# tablet.net
KiCad netlist of a schematic drawn in EAGLE
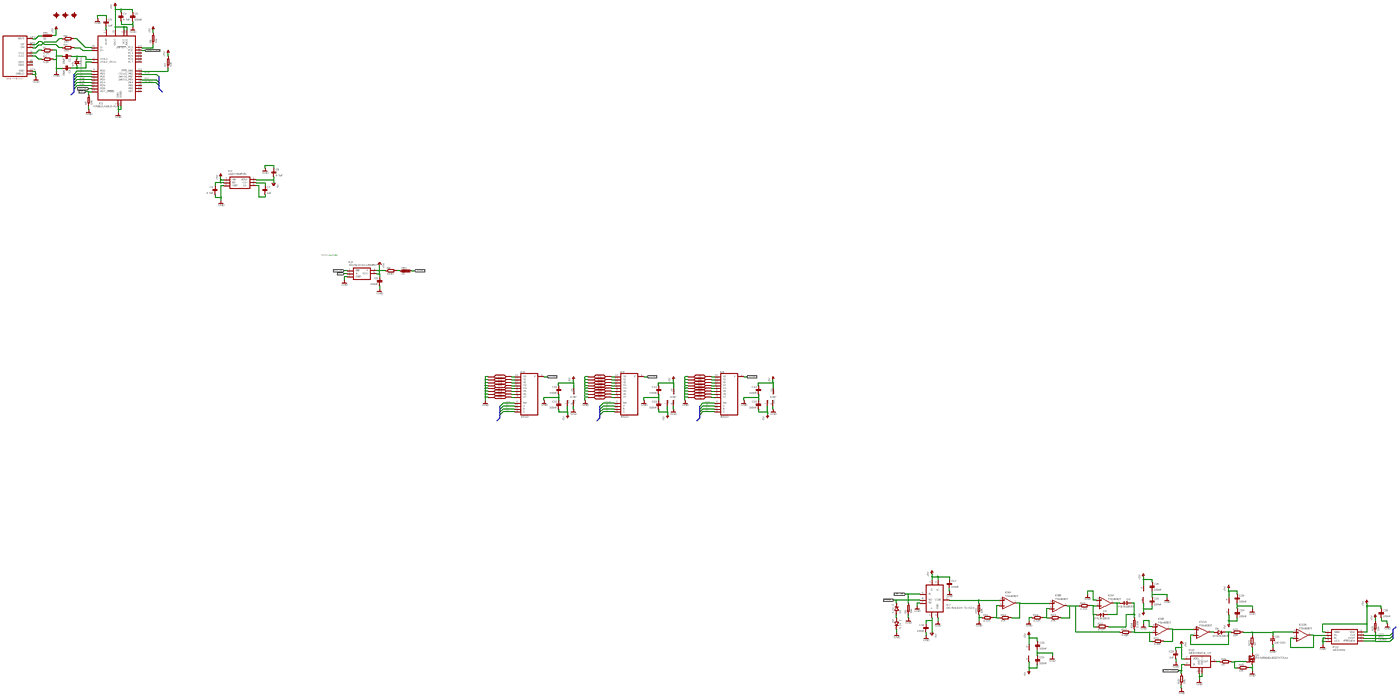
[diagram p0: schematic, sheet 1, overview]
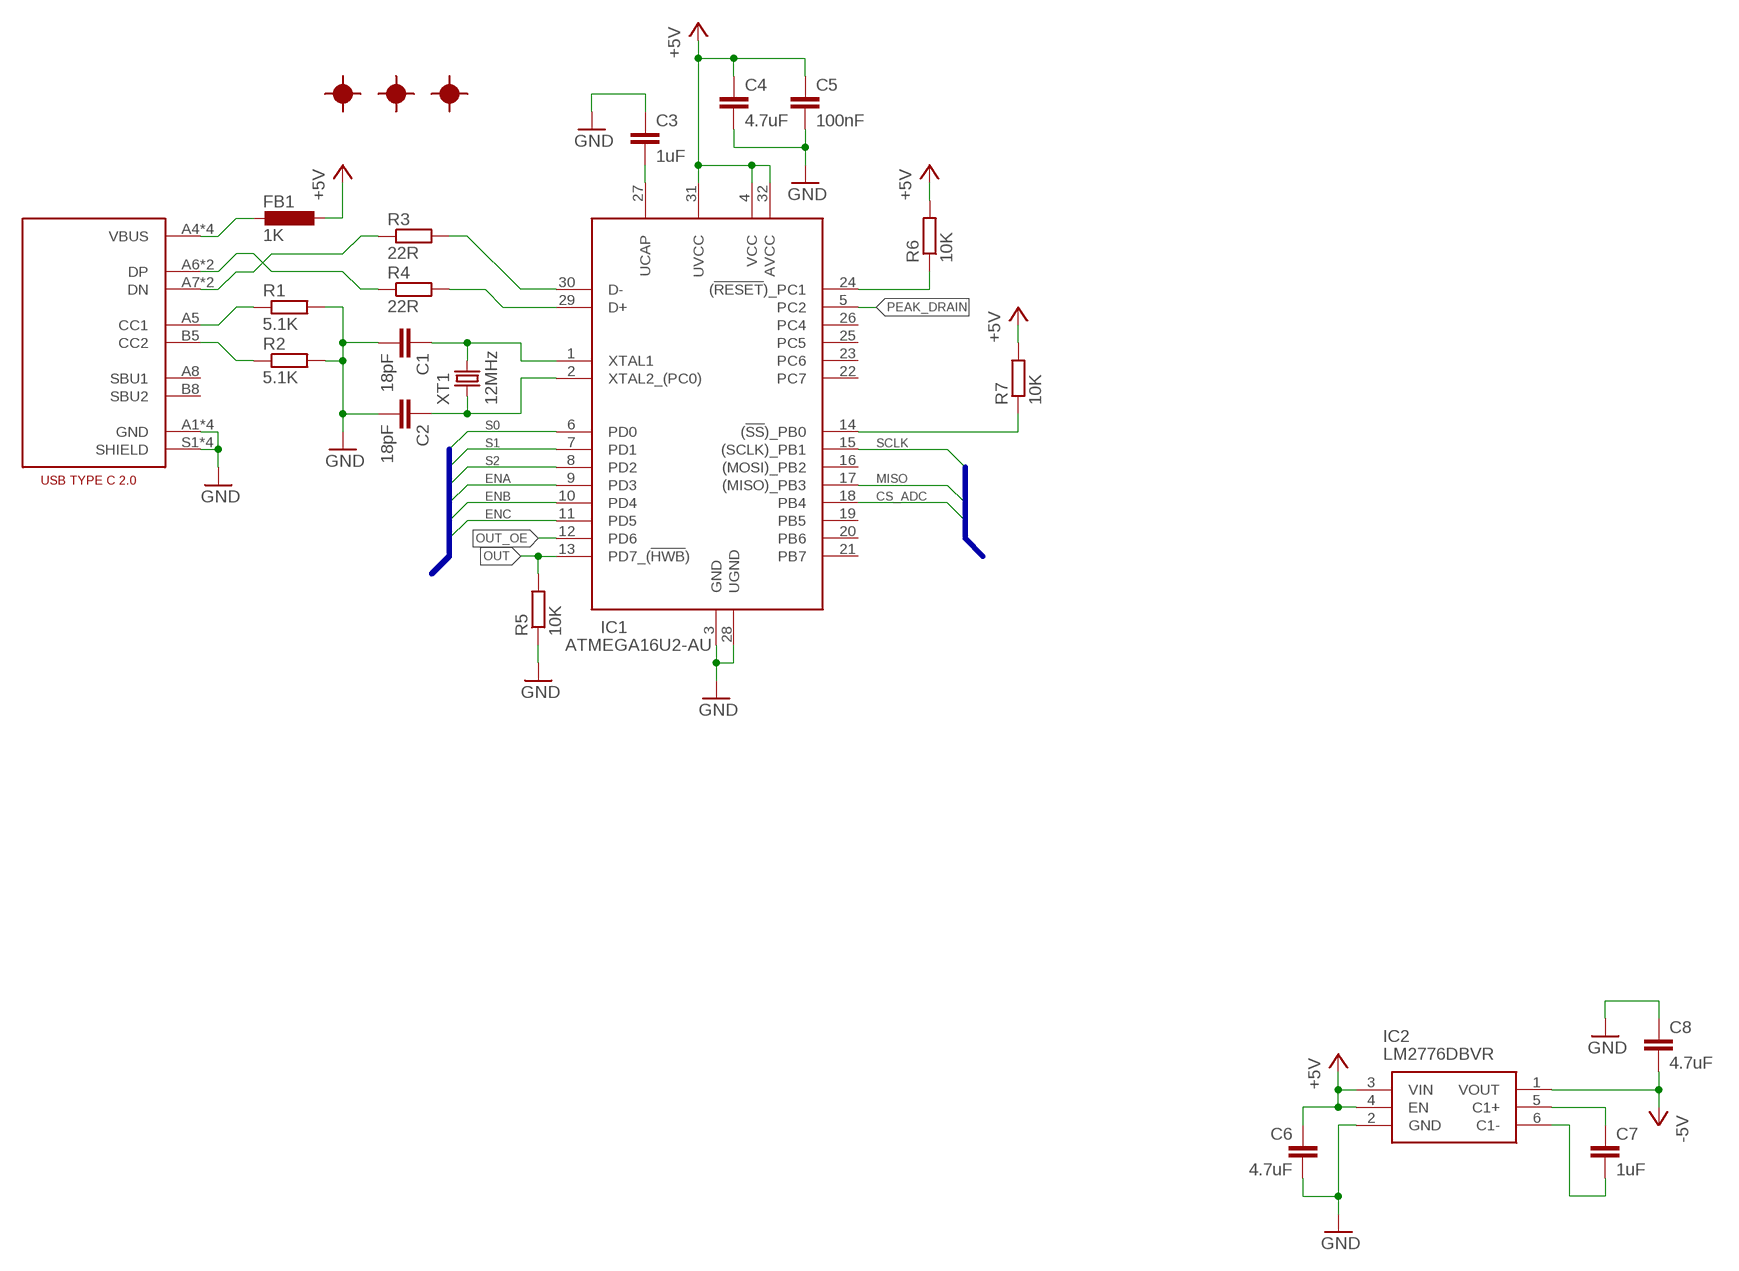
[diagram p1: schematic, sheet 1, part 1 of 4]
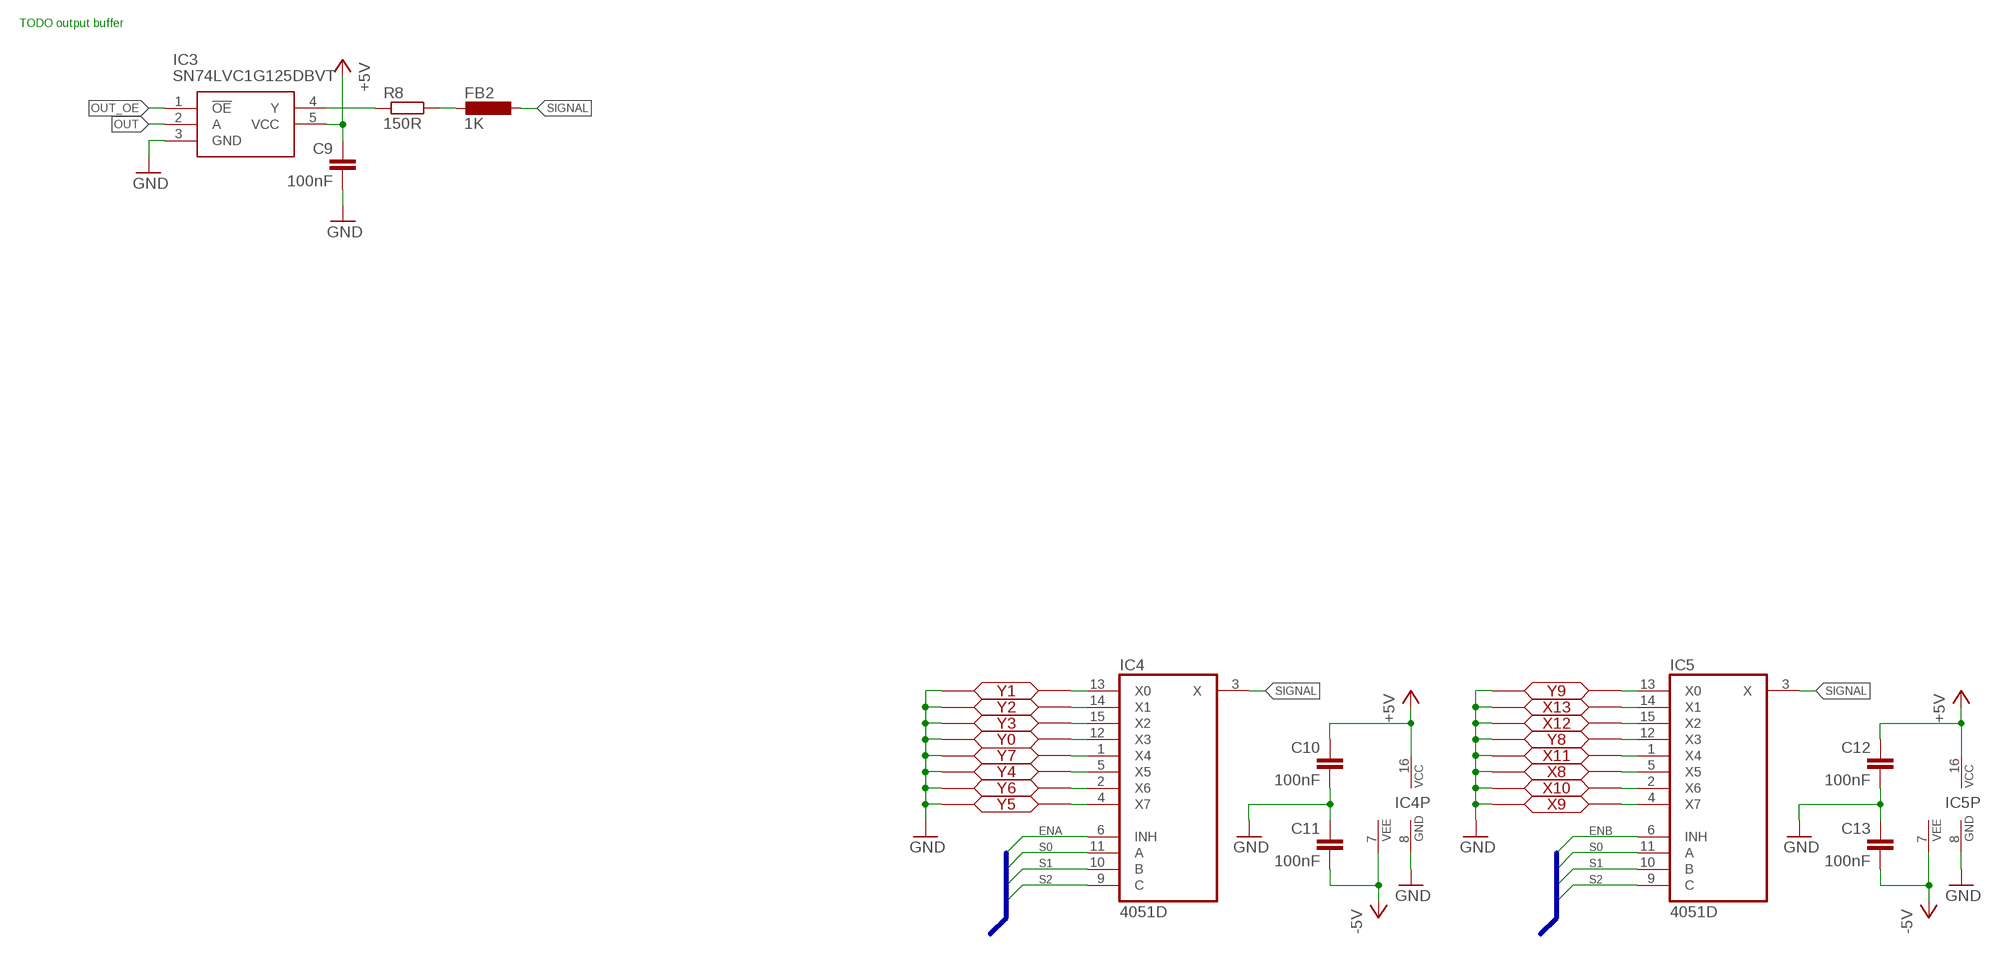
[diagram p2: schematic, sheet 1, part 2 of 4]
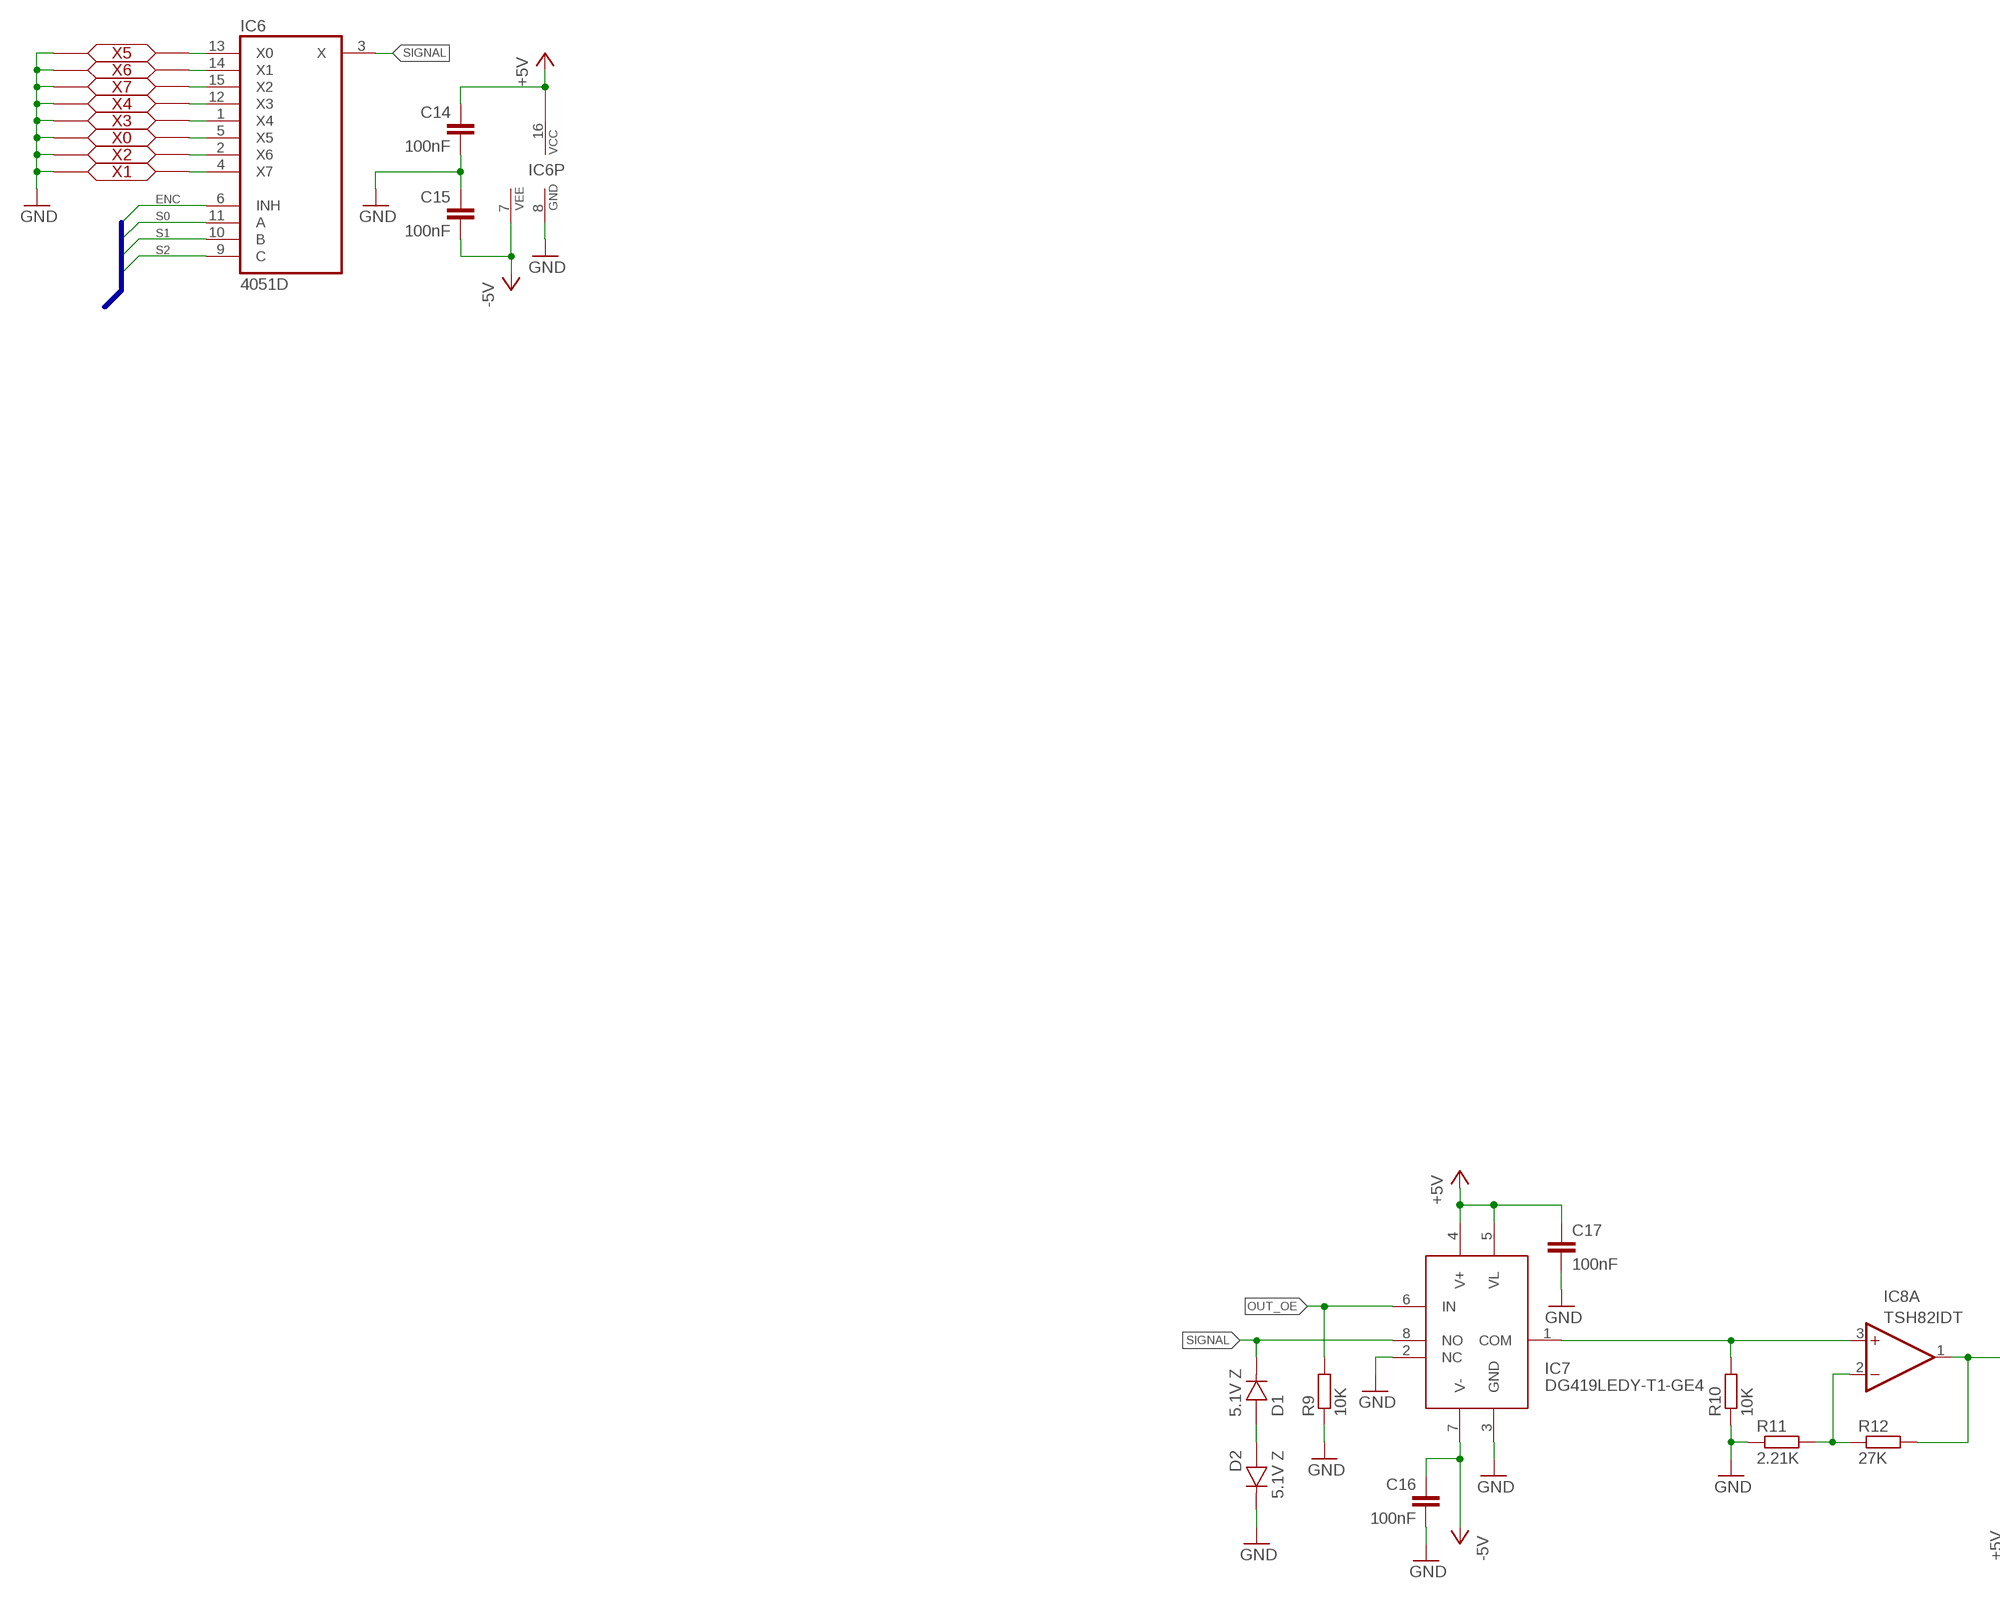
[diagram p3: schematic, sheet 1, part 3 of 4]
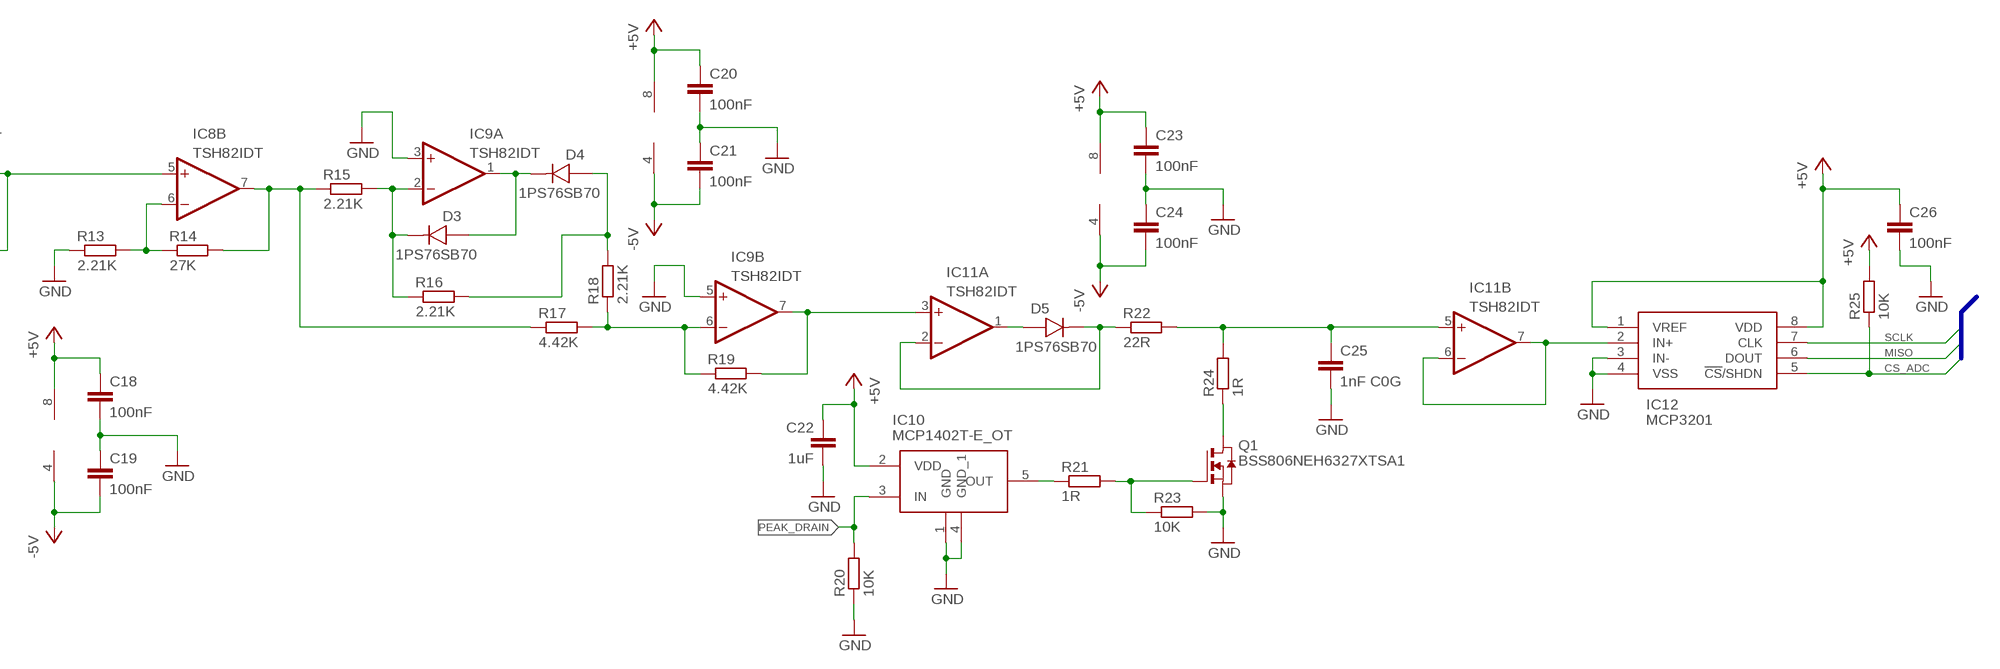
[diagram p4: schematic, sheet 1, part 4 of 4]

(export (version "E")
  (design (tool "Eeschema 10.0.6"))
  (components
    (comp (ref "C1")
      (value "18pF")
      (footprint "eagle-import:0805")
      (libsource (lib "eagle-import") (part "C0805"))
    )
    (comp (ref "C2")
      (value "18pF")
      (footprint "eagle-import:0805")
      (libsource (lib "eagle-import") (part "C0805"))
    )
    (comp (ref "C3")
      (value "1uF")
      (footprint "eagle-import:0805")
      (libsource (lib "eagle-import") (part "C0805"))
    )
    (comp (ref "C4")
      (value "4.7uF")
      (footprint "eagle-import:0805")
      (libsource (lib "eagle-import") (part "C0805"))
    )
    (comp (ref "C5")
      (value "100nF")
      (footprint "eagle-import:0805")
      (libsource (lib "eagle-import") (part "C0805"))
    )
    (comp (ref "C6")
      (value "4.7uF")
      (footprint "eagle-import:0805")
      (libsource (lib "eagle-import") (part "C0805"))
    )
    (comp (ref "C7")
      (value "1uF")
      (footprint "eagle-import:0805")
      (libsource (lib "eagle-import") (part "C0805"))
    )
    (comp (ref "C8")
      (value "4.7uF")
      (footprint "eagle-import:0805")
      (libsource (lib "eagle-import") (part "C0805"))
    )
    (comp (ref "C9")
      (value "100nF")
      (footprint "eagle-import:0805")
      (libsource (lib "eagle-import") (part "C0805"))
    )
    (comp (ref "C10")
      (value "100nF")
      (footprint "eagle-import:0805")
      (libsource (lib "eagle-import") (part "C0805"))
    )
    (comp (ref "C11")
      (value "100nF")
      (footprint "eagle-import:0805")
      (libsource (lib "eagle-import") (part "C0805"))
    )
    (comp (ref "C12")
      (value "100nF")
      (footprint "eagle-import:0805")
      (libsource (lib "eagle-import") (part "C0805"))
    )
    (comp (ref "C13")
      (value "100nF")
      (footprint "eagle-import:0805")
      (libsource (lib "eagle-import") (part "C0805"))
    )
    (comp (ref "C14")
      (value "100nF")
      (footprint "eagle-import:0805")
      (libsource (lib "eagle-import") (part "C0805"))
    )
    (comp (ref "C15")
      (value "100nF")
      (footprint "eagle-import:0805")
      (libsource (lib "eagle-import") (part "C0805"))
    )
    (comp (ref "C16")
      (value "100nF")
      (footprint "eagle-import:0805")
      (libsource (lib "eagle-import") (part "C0805"))
    )
    (comp (ref "C17")
      (value "100nF")
      (footprint "eagle-import:0805")
      (libsource (lib "eagle-import") (part "C0805"))
    )
    (comp (ref "C18")
      (value "100nF")
      (footprint "eagle-import:0805")
      (libsource (lib "eagle-import") (part "C0805"))
    )
    (comp (ref "C19")
      (value "100nF")
      (footprint "eagle-import:0805")
      (libsource (lib "eagle-import") (part "C0805"))
    )
    (comp (ref "C20")
      (value "100nF")
      (footprint "eagle-import:0805")
      (libsource (lib "eagle-import") (part "C0805"))
    )
    (comp (ref "C21")
      (value "100nF")
      (footprint "eagle-import:0805")
      (libsource (lib "eagle-import") (part "C0805"))
    )
    (comp (ref "C22")
      (value "1uF")
      (footprint "eagle-import:0805")
      (libsource (lib "eagle-import") (part "C0805"))
    )
    (comp (ref "C23")
      (value "100nF")
      (footprint "eagle-import:0805")
      (libsource (lib "eagle-import") (part "C0805"))
    )
    (comp (ref "C24")
      (value "100nF")
      (footprint "eagle-import:0805")
      (libsource (lib "eagle-import") (part "C0805"))
    )
    (comp (ref "C25")
      (value "1nF C0G")
      (footprint "eagle-import:0805")
      (libsource (lib "eagle-import") (part "C0805"))
    )
    (comp (ref "C26")
      (value "100nF")
      (footprint "eagle-import:0805")
      (libsource (lib "eagle-import") (part "C0805"))
    )
    (comp (ref "D1")
      (value "5.1V Z")
      (footprint "eagle-import:SOD323")
      (libsource (lib "eagle-import") (part "DSOD323"))
    )
    (comp (ref "D2")
      (value "5.1V Z")
      (footprint "eagle-import:SOD323")
      (libsource (lib "eagle-import") (part "DSOD323"))
    )
    (comp (ref "D3")
      (value "1PS76SB70")
      (footprint "eagle-import:SOD323")
      (libsource (lib "eagle-import") (part "DSOD323"))
    )
    (comp (ref "D4")
      (value "1PS76SB70")
      (footprint "eagle-import:SOD323")
      (libsource (lib "eagle-import") (part "DSOD323"))
    )
    (comp (ref "D5")
      (value "1PS76SB70")
      (footprint "eagle-import:SOD323")
      (libsource (lib "eagle-import") (part "DSOD323"))
    )
    (comp (ref "FB1")
      (value "1K")
      (footprint "eagle-import:0805")
      (libsource (lib "eagle-import") (part "FB0805"))
    )
    (comp (ref "FB2")
      (value "1K")
      (footprint "eagle-import:0805")
      (libsource (lib "eagle-import") (part "FB0805"))
    )
    (comp (ref "FD1")
      (value "FIDUCIAL1_2")
      (footprint "eagle-import:FIDUCIAL")
      (libsource (lib "eagle-import") (part "FIDUCIAL1_2"))
    )
    (comp (ref "FD2")
      (value "FIDUCIAL1_2")
      (footprint "eagle-import:FIDUCIAL")
      (libsource (lib "eagle-import") (part "FIDUCIAL1_2"))
    )
    (comp (ref "FD3")
      (value "FIDUCIAL1_2")
      (footprint "eagle-import:FIDUCIAL")
      (libsource (lib "eagle-import") (part "FIDUCIAL1_2"))
    )
    (comp (ref "IC1")
      (value "ATMEGA16U2-AU")
      (footprint "eagle-import:QFP80P900X900X120-32N")
      (fields
        (field (name "MOUSER_PART_NUMBER") "556-ATMEGA16U2-AU")
        (field (name "RS_PART_NUMBER") "1278282P")
      )
      (libsource (lib "eagle-import") (part "ATMEGA16U2-AU"))
    )
    (comp (ref "IC2")
      (value "LM2776DBVR")
      (footprint "eagle-import:SOT95P280X145-6N")
      (fields (field (name "MOUSER_PART_NUMBER") "595-LM2776DBVR"))
      (libsource (lib "eagle-import") (part "LM2776DBVR"))
    )
    (comp (ref "IC3")
      (value "SN74LVC1G125DBVT")
      (footprint "eagle-import:SOT95P280X145-5N")
      (fields (field (name "MOUSER_PART_NUMBER") "595-SN74LVC1G125DBVT"))
      (libsource (lib "eagle-import") (part "SN74LVC1G125DBVT"))
    )
    (comp (ref "IC4")
      (value "4051D")
      (footprint "eagle-import:SO16")
      (libsource (lib "eagle-import") (part "4051D"))
    )
    (comp (ref "IC5")
      (value "4051D")
      (footprint "eagle-import:SO16")
      (libsource (lib "eagle-import") (part "4051D"))
    )
    (comp (ref "IC6")
      (value "4051D")
      (footprint "eagle-import:SO16")
      (libsource (lib "eagle-import") (part "4051D"))
    )
    (comp (ref "IC7")
      (value "DG419LEDY-T1-GE4")
      (footprint "eagle-import:SOIC8")
      (libsource (lib "eagle-import") (part "DG419LEDY-T1-GE4"))
    )
    (comp (ref "IC8")
      (value "TSH82IDT")
      (footprint "eagle-import:SOIC8")
      (libsource (lib "eagle-import") (part "OPAMPSOIC8"))
    )
    (comp (ref "IC9")
      (value "TSH82IDT")
      (footprint "eagle-import:SOIC8")
      (libsource (lib "eagle-import") (part "OPAMPSOIC8"))
    )
    (comp (ref "IC10")
      (value "MCP1402T-E_OT")
      (footprint "eagle-import:SOT95P270X145-5N")
      (fields
        (field (name "ARROW_PART_NUMBER") "MCP1402T-E/OT")
        (field (name "MOUSER_PART_NUMBER") "579-MCP1402T-E/OT")
      )
      (libsource (lib "eagle-import") (part "MCP1402T-E_OT"))
    )
    (comp (ref "IC11")
      (value "TSH82IDT")
      (footprint "eagle-import:SOIC8")
      (libsource (lib "eagle-import") (part "OPAMPSOIC8"))
    )
    (comp (ref "IC12")
      (value "MCP3201")
      (footprint "eagle-import:SOIC8")
      (libsource (lib "eagle-import") (part "MCP3201"))
    )
    (comp (ref "J1")
      (value "USB4085-GF-A")
      (footprint "eagle-import:USB4085-GF-A")
      (libsource (lib "eagle-import") (part "USB4085-GF-A"))
    )
    (comp (ref "Q1")
      (value "BSS806NEH6327XTSA1")
      (footprint "eagle-import:SOT23_3")
      (libsource (lib "eagle-import") (part "MOSFET_NSOT23_3_GSD"))
    )
    (comp (ref "R1")
      (value "5.1K")
      (footprint "eagle-import:0805")
      (libsource (lib "eagle-import") (part "R0805"))
    )
    (comp (ref "R2")
      (value "5.1K")
      (footprint "eagle-import:0805")
      (libsource (lib "eagle-import") (part "R0805"))
    )
    (comp (ref "R3")
      (value "22R")
      (footprint "eagle-import:0805")
      (libsource (lib "eagle-import") (part "R0805"))
    )
    (comp (ref "R4")
      (value "22R")
      (footprint "eagle-import:0805")
      (libsource (lib "eagle-import") (part "R0805"))
    )
    (comp (ref "R5")
      (value "10K")
      (footprint "eagle-import:0805")
      (libsource (lib "eagle-import") (part "R0805"))
    )
    (comp (ref "R6")
      (value "10K")
      (footprint "eagle-import:0805")
      (libsource (lib "eagle-import") (part "R0805"))
    )
    (comp (ref "R7")
      (value "10K")
      (footprint "eagle-import:0805")
      (libsource (lib "eagle-import") (part "R0805"))
    )
    (comp (ref "R8")
      (value "150R")
      (footprint "eagle-import:0805")
      (libsource (lib "eagle-import") (part "R0805"))
    )
    (comp (ref "R9")
      (value "10K")
      (footprint "eagle-import:0805")
      (libsource (lib "eagle-import") (part "R0805"))
    )
    (comp (ref "R10")
      (value "10K")
      (footprint "eagle-import:0805")
      (libsource (lib "eagle-import") (part "R0805"))
    )
    (comp (ref "R11")
      (value "2.21K")
      (footprint "eagle-import:0805")
      (libsource (lib "eagle-import") (part "R0805"))
    )
    (comp (ref "R12")
      (value "27K")
      (footprint "eagle-import:0805")
      (libsource (lib "eagle-import") (part "R0805"))
    )
    (comp (ref "R13")
      (value "2.21K")
      (footprint "eagle-import:0805")
      (libsource (lib "eagle-import") (part "R0805"))
    )
    (comp (ref "R14")
      (value "27K")
      (footprint "eagle-import:0805")
      (libsource (lib "eagle-import") (part "R0805"))
    )
    (comp (ref "R15")
      (value "2.21K")
      (footprint "eagle-import:0805")
      (libsource (lib "eagle-import") (part "R0805"))
    )
    (comp (ref "R16")
      (value "2.21K")
      (footprint "eagle-import:0805")
      (libsource (lib "eagle-import") (part "R0805"))
    )
    (comp (ref "R17")
      (value "4.42K")
      (footprint "eagle-import:0805")
      (libsource (lib "eagle-import") (part "R0805"))
    )
    (comp (ref "R18")
      (value "2.21K")
      (footprint "eagle-import:0805")
      (libsource (lib "eagle-import") (part "R0805"))
    )
    (comp (ref "R19")
      (value "4.42K")
      (footprint "eagle-import:0805")
      (libsource (lib "eagle-import") (part "R0805"))
    )
    (comp (ref "R20")
      (value "10K")
      (footprint "eagle-import:0805")
      (libsource (lib "eagle-import") (part "R0805"))
    )
    (comp (ref "R21")
      (value "1R")
      (footprint "eagle-import:0805")
      (libsource (lib "eagle-import") (part "R0805"))
    )
    (comp (ref "R22")
      (value "22R")
      (footprint "eagle-import:0805")
      (libsource (lib "eagle-import") (part "R0805"))
    )
    (comp (ref "R23")
      (value "10K")
      (footprint "eagle-import:0805")
      (libsource (lib "eagle-import") (part "R0805"))
    )
    (comp (ref "R24")
      (value "1R")
      (footprint "eagle-import:0805")
      (libsource (lib "eagle-import") (part "R0805"))
    )
    (comp (ref "R25")
      (value "10K")
      (footprint "eagle-import:0805")
      (libsource (lib "eagle-import") (part "R0805"))
    )
    (comp (ref "X0") (value "2P") (footprint "eagle-import:2P") (libsource (lib "eagle-import") (part "2P")))
    (comp (ref "X1") (value "2P") (footprint "eagle-import:2P") (libsource (lib "eagle-import") (part "2P")))
    (comp (ref "X2") (value "2P") (footprint "eagle-import:2P") (libsource (lib "eagle-import") (part "2P")))
    (comp (ref "X3") (value "2P") (footprint "eagle-import:2P") (libsource (lib "eagle-import") (part "2P")))
    (comp (ref "X4") (value "2P") (footprint "eagle-import:2P") (libsource (lib "eagle-import") (part "2P")))
    (comp (ref "X5") (value "2P") (footprint "eagle-import:2P") (libsource (lib "eagle-import") (part "2P")))
    (comp (ref "X6") (value "2P") (footprint "eagle-import:2P") (libsource (lib "eagle-import") (part "2P")))
    (comp (ref "X7") (value "2P") (footprint "eagle-import:2P") (libsource (lib "eagle-import") (part "2P")))
    (comp (ref "X8") (value "2P") (footprint "eagle-import:2P") (libsource (lib "eagle-import") (part "2P")))
    (comp (ref "X9") (value "2P") (footprint "eagle-import:2P") (libsource (lib "eagle-import") (part "2P")))
    (comp (ref "X10") (value "2P") (footprint "eagle-import:2P") (libsource (lib "eagle-import") (part "2P")))
    (comp (ref "X11") (value "2P") (footprint "eagle-import:2P") (libsource (lib "eagle-import") (part "2P")))
    (comp (ref "X12") (value "2P") (footprint "eagle-import:2P") (libsource (lib "eagle-import") (part "2P")))
    (comp (ref "X13") (value "2P") (footprint "eagle-import:2P") (libsource (lib "eagle-import") (part "2P")))
    (comp (ref "XT1")
      (value "12MHz")
      (footprint "eagle-import:HC49UP")
      (libsource (lib "eagle-import") (part "CRYSTALHC49UP"))
    )
    (comp (ref "Y0") (value "2P") (footprint "eagle-import:2P") (libsource (lib "eagle-import") (part "2P")))
    (comp (ref "Y1") (value "2P") (footprint "eagle-import:2P") (libsource (lib "eagle-import") (part "2P")))
    (comp (ref "Y2") (value "2P") (footprint "eagle-import:2P") (libsource (lib "eagle-import") (part "2P")))
    (comp (ref "Y3") (value "2P") (footprint "eagle-import:2P") (libsource (lib "eagle-import") (part "2P")))
    (comp (ref "Y4") (value "2P") (footprint "eagle-import:2P") (libsource (lib "eagle-import") (part "2P")))
    (comp (ref "Y5") (value "2P") (footprint "eagle-import:2P") (libsource (lib "eagle-import") (part "2P")))
    (comp (ref "Y6") (value "2P") (footprint "eagle-import:2P") (libsource (lib "eagle-import") (part "2P")))
    (comp (ref "Y7") (value "2P") (footprint "eagle-import:2P") (libsource (lib "eagle-import") (part "2P")))
    (comp (ref "Y8") (value "2P") (footprint "eagle-import:2P") (libsource (lib "eagle-import") (part "2P")))
    (comp (ref "Y9") (value "2P") (footprint "eagle-import:2P") (libsource (lib "eagle-import") (part "2P")))
  )
  (nets
    (net (code "1") (name "+5V") (class "Default")
      (node (ref "C10") (pin "1") (pinfunction "1_1") (pintype "passive"))
      (node (ref "C12") (pin "1") (pinfunction "1_1") (pintype "passive"))
      (node (ref "C14") (pin "1") (pinfunction "1_1") (pintype "passive"))
      (node (ref "C17") (pin "1") (pinfunction "1_1") (pintype "passive"))
      (node (ref "C18") (pin "1") (pinfunction "1_1") (pintype "passive"))
      (node (ref "C20") (pin "1") (pinfunction "1_1") (pintype "passive"))
      (node (ref "C22") (pin "1") (pinfunction "1_1") (pintype "passive"))
      (node (ref "C23") (pin "1") (pinfunction "1_1") (pintype "passive"))
      (node (ref "C26") (pin "1") (pinfunction "1_1") (pintype "passive"))
      (node (ref "C4") (pin "1") (pinfunction "1_1") (pintype "passive"))
      (node (ref "C5") (pin "1") (pinfunction "1_1") (pintype "passive"))
      (node (ref "C6") (pin "1") (pinfunction "1_1") (pintype "passive"))
      (node (ref "C9") (pin "1") (pinfunction "1_1") (pintype "passive"))
      (node (ref "FB1") (pin "1") (pinfunction "1_1") (pintype "passive"))
      (node (ref "IC1") (pin "31") (pinfunction "UVCC_31") (pintype "bidirectional"))
      (node (ref "IC1") (pin "32") (pinfunction "AVCC_32") (pintype "bidirectional"))
      (node (ref "IC1") (pin "4") (pinfunction "VCC_4") (pintype "bidirectional"))
      (node (ref "IC10") (pin "2") (pinfunction "VDD_2") (pintype "power_in"))
      (node (ref "IC11") (pin "8") (pinfunction "V+_8") (pintype "power_in"))
      (node (ref "IC12") (pin "1") (pinfunction "VREF_1") (pintype "input"))
      (node (ref "IC12") (pin "8") (pinfunction "VDD_8") (pintype "power_in"))
      (node (ref "IC2") (pin "3") (pinfunction "VIN_3") (pintype "bidirectional"))
      (node (ref "IC2") (pin "4") (pinfunction "EN_4") (pintype "bidirectional"))
      (node (ref "IC3") (pin "5") (pinfunction "VCC_5") (pintype "bidirectional"))
      (node (ref "IC4") (pin "16") (pinfunction "VCC_16") (pintype "power_in"))
      (node (ref "IC5") (pin "16") (pinfunction "VCC_16") (pintype "power_in"))
      (node (ref "IC6") (pin "16") (pinfunction "VCC_16") (pintype "power_in"))
      (node (ref "IC7") (pin "4") (pinfunction "V+_4") (pintype "bidirectional"))
      (node (ref "IC7") (pin "5") (pinfunction "VL_5") (pintype "bidirectional"))
      (node (ref "IC8") (pin "8") (pinfunction "V+_8") (pintype "power_in"))
      (node (ref "IC9") (pin "8") (pinfunction "V+_8") (pintype "power_in"))
      (node (ref "R25") (pin "2") (pinfunction "2_2") (pintype "passive"))
      (node (ref "R6") (pin "2") (pinfunction "2_2") (pintype "passive"))
      (node (ref "R7") (pin "2") (pinfunction "2_2") (pintype "passive"))
    )
    (net (code "2") (name "-5V") (class "Default")
      (node (ref "C11") (pin "2") (pinfunction "2_2") (pintype "passive"))
      (node (ref "C13") (pin "2") (pinfunction "2_2") (pintype "passive"))
      (node (ref "C15") (pin "2") (pinfunction "2_2") (pintype "passive"))
      (node (ref "C16") (pin "1") (pinfunction "1_1") (pintype "passive"))
      (node (ref "C19") (pin "2") (pinfunction "2_2") (pintype "passive"))
      (node (ref "C21") (pin "2") (pinfunction "2_2") (pintype "passive"))
      (node (ref "C24") (pin "2") (pinfunction "2_2") (pintype "passive"))
      (node (ref "C8") (pin "2") (pinfunction "2_2") (pintype "passive"))
      (node (ref "IC11") (pin "4") (pinfunction "V-_4") (pintype "power_in"))
      (node (ref "IC2") (pin "1") (pinfunction "VOUT_1") (pintype "bidirectional"))
      (node (ref "IC4") (pin "7") (pinfunction "VEE_7") (pintype "power_in"))
      (node (ref "IC5") (pin "7") (pinfunction "VEE_7") (pintype "power_in"))
      (node (ref "IC6") (pin "7") (pinfunction "VEE_7") (pintype "power_in"))
      (node (ref "IC7") (pin "7") (pinfunction "V-_7") (pintype "bidirectional"))
      (node (ref "IC8") (pin "4") (pinfunction "V-_4") (pintype "power_in"))
      (node (ref "IC9") (pin "4") (pinfunction "V-_4") (pintype "power_in"))
    )
    (net (code "5") (name "CS_ADC") (class "Default")
      (node (ref "IC1") (pin "18") (pinfunction "PB4_18") (pintype "bidirectional"))
      (node (ref "IC12") (pin "5") (pinfunction "~{CS}/SHDN_5") (pintype "input"))
      (node (ref "R25") (pin "1") (pinfunction "1_1") (pintype "passive"))
    )
    (net (code "6") (name "ENA") (class "Default")
      (node (ref "IC1") (pin "9") (pinfunction "PD3_9") (pintype "bidirectional"))
      (node (ref "IC4") (pin "6") (pinfunction "INH_6") (pintype "input"))
    )
    (net (code "7") (name "ENB") (class "Default")
      (node (ref "IC1") (pin "10") (pinfunction "PD4_10") (pintype "bidirectional"))
      (node (ref "IC5") (pin "6") (pinfunction "INH_6") (pintype "input"))
    )
    (net (code "8") (name "ENC") (class "Default")
      (node (ref "IC1") (pin "11") (pinfunction "PD5_11") (pintype "bidirectional"))
      (node (ref "IC6") (pin "6") (pinfunction "INH_6") (pintype "input"))
    )
    (net (code "9") (name "GND") (class "Default")
      (node (ref "C1") (pin "2") (pinfunction "2_2") (pintype "passive"))
      (node (ref "C10") (pin "2") (pinfunction "2_2") (pintype "passive"))
      (node (ref "C11") (pin "1") (pinfunction "1_1") (pintype "passive"))
      (node (ref "C12") (pin "2") (pinfunction "2_2") (pintype "passive"))
      (node (ref "C13") (pin "1") (pinfunction "1_1") (pintype "passive"))
      (node (ref "C14") (pin "2") (pinfunction "2_2") (pintype "passive"))
      (node (ref "C15") (pin "1") (pinfunction "1_1") (pintype "passive"))
      (node (ref "C16") (pin "2") (pinfunction "2_2") (pintype "passive"))
      (node (ref "C17") (pin "2") (pinfunction "2_2") (pintype "passive"))
      (node (ref "C18") (pin "2") (pinfunction "2_2") (pintype "passive"))
      (node (ref "C19") (pin "1") (pinfunction "1_1") (pintype "passive"))
      (node (ref "C2") (pin "2") (pinfunction "2_2") (pintype "passive"))
      (node (ref "C20") (pin "2") (pinfunction "2_2") (pintype "passive"))
      (node (ref "C21") (pin "1") (pinfunction "1_1") (pintype "passive"))
      (node (ref "C22") (pin "2") (pinfunction "2_2") (pintype "passive"))
      (node (ref "C23") (pin "2") (pinfunction "2_2") (pintype "passive"))
      (node (ref "C24") (pin "1") (pinfunction "1_1") (pintype "passive"))
      (node (ref "C25") (pin "2") (pinfunction "2_2") (pintype "passive"))
      (node (ref "C26") (pin "2") (pinfunction "2_2") (pintype "passive"))
      (node (ref "C3") (pin "1") (pinfunction "1_1") (pintype "passive"))
      (node (ref "C4") (pin "2") (pinfunction "2_2") (pintype "passive"))
      (node (ref "C5") (pin "2") (pinfunction "2_2") (pintype "passive"))
      (node (ref "C6") (pin "2") (pinfunction "2_2") (pintype "passive"))
      (node (ref "C8") (pin "1") (pinfunction "1_1") (pintype "passive"))
      (node (ref "C9") (pin "2") (pinfunction "2_2") (pintype "passive"))
      (node (ref "D2") (pin "2") (pinfunction "2_2") (pintype "passive"))
      (node (ref "IC1") (pin "28") (pinfunction "UGND_28") (pintype "bidirectional"))
      (node (ref "IC1") (pin "3") (pinfunction "GND_3") (pintype "bidirectional"))
      (node (ref "IC10") (pin "1") (pinfunction "GND_1") (pintype "power_in"))
      (node (ref "IC10") (pin "4") (pinfunction "GND_1_4") (pintype "power_in"))
      (node (ref "IC12") (pin "3") (pinfunction "IN-_3") (pintype "input"))
      (node (ref "IC12") (pin "4") (pinfunction "VSS_4") (pintype "power_in"))
      (node (ref "IC2") (pin "2") (pinfunction "GND_2") (pintype "bidirectional"))
      (node (ref "IC3") (pin "3") (pinfunction "GND_3") (pintype "bidirectional"))
      (node (ref "IC4") (pin "8") (pinfunction "GND_8") (pintype "power_in"))
      (node (ref "IC5") (pin "8") (pinfunction "GND_8") (pintype "power_in"))
      (node (ref "IC6") (pin "8") (pinfunction "GND_8") (pintype "power_in"))
      (node (ref "IC7") (pin "2") (pinfunction "NC_2") (pintype "bidirectional"))
      (node (ref "IC7") (pin "3") (pinfunction "GND_3") (pintype "bidirectional"))
      (node (ref "IC9") (pin "3") (pinfunction "+IN_3") (pintype "input"))
      (node (ref "IC9") (pin "5") (pinfunction "+IN_5") (pintype "input"))
      (node (ref "J1") (pin "A1") (pinfunction "GND_A1") (pintype "bidirectional"))
      (node (ref "J1") (pin "A12") (pinfunction "GND_A12") (pintype "bidirectional"))
      (node (ref "J1") (pin "B1") (pinfunction "GND_B1") (pintype "bidirectional"))
      (node (ref "J1") (pin "B12") (pinfunction "GND_B12") (pintype "bidirectional"))
      (node (ref "J1") (pin "S1") (pinfunction "SHIELD_S1") (pintype "bidirectional"))
      (node (ref "J1") (pin "S2") (pinfunction "SHIELD_S2") (pintype "bidirectional"))
      (node (ref "J1") (pin "S3") (pinfunction "SHIELD_S3") (pintype "bidirectional"))
      (node (ref "J1") (pin "S4") (pinfunction "SHIELD_S4") (pintype "bidirectional"))
      (node (ref "Q1") (pin "P$2") (pinfunction "S_P$2") (pintype "passive"))
      (node (ref "R1") (pin "2") (pinfunction "2_2") (pintype "passive"))
      (node (ref "R10") (pin "1") (pinfunction "1_1") (pintype "passive"))
      (node (ref "R11") (pin "1") (pinfunction "1_1") (pintype "passive"))
      (node (ref "R13") (pin "1") (pinfunction "1_1") (pintype "passive"))
      (node (ref "R2") (pin "2") (pinfunction "2_2") (pintype "passive"))
      (node (ref "R20") (pin "1") (pinfunction "1_1") (pintype "passive"))
      (node (ref "R23") (pin "2") (pinfunction "2_2") (pintype "passive"))
      (node (ref "R5") (pin "1") (pinfunction "1_1") (pintype "passive"))
      (node (ref "R9") (pin "1") (pinfunction "1_1") (pintype "passive"))
      (node (ref "X0") (pin "2") (pinfunction "2_2") (pintype "bidirectional"))
      (node (ref "X1") (pin "2") (pinfunction "2_2") (pintype "bidirectional"))
      (node (ref "X10") (pin "2") (pinfunction "2_2") (pintype "bidirectional"))
      (node (ref "X11") (pin "2") (pinfunction "2_2") (pintype "bidirectional"))
      (node (ref "X12") (pin "2") (pinfunction "2_2") (pintype "bidirectional"))
      (node (ref "X13") (pin "2") (pinfunction "2_2") (pintype "bidirectional"))
      (node (ref "X2") (pin "2") (pinfunction "2_2") (pintype "bidirectional"))
      (node (ref "X3") (pin "2") (pinfunction "2_2") (pintype "bidirectional"))
      (node (ref "X4") (pin "2") (pinfunction "2_2") (pintype "bidirectional"))
      (node (ref "X5") (pin "2") (pinfunction "2_2") (pintype "bidirectional"))
      (node (ref "X6") (pin "2") (pinfunction "2_2") (pintype "bidirectional"))
      (node (ref "X7") (pin "2") (pinfunction "2_2") (pintype "bidirectional"))
      (node (ref "X8") (pin "2") (pinfunction "2_2") (pintype "bidirectional"))
      (node (ref "X9") (pin "2") (pinfunction "2_2") (pintype "bidirectional"))
      (node (ref "Y0") (pin "2") (pinfunction "2_2") (pintype "bidirectional"))
      (node (ref "Y1") (pin "2") (pinfunction "2_2") (pintype "bidirectional"))
      (node (ref "Y2") (pin "2") (pinfunction "2_2") (pintype "bidirectional"))
      (node (ref "Y3") (pin "2") (pinfunction "2_2") (pintype "bidirectional"))
      (node (ref "Y4") (pin "2") (pinfunction "2_2") (pintype "bidirectional"))
      (node (ref "Y5") (pin "2") (pinfunction "2_2") (pintype "bidirectional"))
      (node (ref "Y6") (pin "2") (pinfunction "2_2") (pintype "bidirectional"))
      (node (ref "Y7") (pin "2") (pinfunction "2_2") (pintype "bidirectional"))
      (node (ref "Y8") (pin "2") (pinfunction "2_2") (pintype "bidirectional"))
      (node (ref "Y9") (pin "2") (pinfunction "2_2") (pintype "bidirectional"))
    )
    (net (code "10") (name "MISO") (class "Default")
      (node (ref "IC1") (pin "17") (pinfunction "(MISO)_PB3_17") (pintype "bidirectional"))
      (node (ref "IC12") (pin "6") (pinfunction "DOUT_6") (pintype "output"))
    )
    (net (code "11") (name "Net-(D1-Pad1)") (class "Default")
      (node (ref "D1") (pin "1") (pinfunction "1_1") (pintype "passive"))
      (node (ref "D2") (pin "1") (pinfunction "1_1") (pintype "passive"))
    )
    (net (code "12") (name "Net-(D4-Pad1)") (class "Default")
      (node (ref "D4") (pin "1") (pinfunction "1_1") (pintype "passive"))
      (node (ref "R16") (pin "2") (pinfunction "2_2") (pintype "passive"))
      (node (ref "R18") (pin "2") (pinfunction "2_2") (pintype "passive"))
    )
    (net (code "13") (name "Net-(FB1-Pad2)") (class "Default")
      (node (ref "FB1") (pin "2") (pinfunction "2_2") (pintype "passive"))
      (node (ref "J1") (pin "A4") (pinfunction "VBUS_A4") (pintype "bidirectional"))
      (node (ref "J1") (pin "A9") (pinfunction "VBUS_A9") (pintype "bidirectional"))
      (node (ref "J1") (pin "B4") (pinfunction "VBUS_B4") (pintype "bidirectional"))
      (node (ref "J1") (pin "B9") (pinfunction "VBUS_B9") (pintype "bidirectional"))
    )
    (net (code "14") (name "Net-(FB2-Pad2)") (class "Default")
      (node (ref "FB2") (pin "2") (pinfunction "2_2") (pintype "passive"))
      (node (ref "R8") (pin "2") (pinfunction "2_2") (pintype "passive"))
    )
    (net (code "15") (name "Net-(IC1-(~{RESET})_PC1)") (class "Default")
      (node (ref "IC1") (pin "24") (pinfunction "(~{RESET})_PC1_24") (pintype "bidirectional"))
      (node (ref "R6") (pin "1") (pinfunction "1_1") (pintype "passive"))
    )
    (net (code "16") (name "Net-(IC1-(~{SS})_PB0)") (class "Default")
      (node (ref "IC1") (pin "14") (pinfunction "(~{SS})_PB0_14") (pintype "bidirectional"))
      (node (ref "R7") (pin "1") (pinfunction "1_1") (pintype "passive"))
    )
    (net (code "17") (name "Net-(IC1-D+)") (class "Default")
      (node (ref "IC1") (pin "29") (pinfunction "D+_29") (pintype "bidirectional"))
      (node (ref "R4") (pin "2") (pinfunction "2_2") (pintype "passive"))
    )
    (net (code "18") (name "Net-(IC1-D-)") (class "Default")
      (node (ref "IC1") (pin "30") (pinfunction "D-_30") (pintype "bidirectional"))
      (node (ref "R3") (pin "2") (pinfunction "2_2") (pintype "passive"))
    )
    (net (code "19") (name "Net-(IC1-UCAP)") (class "Default")
      (node (ref "C3") (pin "2") (pinfunction "2_2") (pintype "passive"))
      (node (ref "IC1") (pin "27") (pinfunction "UCAP_27") (pintype "bidirectional"))
    )
    (net (code "20") (name "Net-(IC1-XTAL1)") (class "Default")
      (node (ref "C1") (pin "1") (pinfunction "1_1") (pintype "passive"))
      (node (ref "IC1") (pin "1") (pinfunction "XTAL1_1") (pintype "bidirectional"))
      (node (ref "XT1") (pin "2") (pinfunction "2_2") (pintype "passive"))
    )
    (net (code "21") (name "Net-(IC1-XTAL2_(PC0))") (class "Default")
      (node (ref "C2") (pin "1") (pinfunction "1_1") (pintype "passive"))
      (node (ref "IC1") (pin "2") (pinfunction "XTAL2_(PC0)_2") (pintype "bidirectional"))
      (node (ref "XT1") (pin "1") (pinfunction "1_1") (pintype "passive"))
    )
    (net (code "22") (name "Net-(IC2-C1+)") (class "Default")
      (node (ref "C7") (pin "1") (pinfunction "1_1") (pintype "passive"))
      (node (ref "IC2") (pin "5") (pinfunction "C1+_5") (pintype "bidirectional"))
    )
    (net (code "23") (name "Net-(IC2-C1-)") (class "Default")
      (node (ref "C7") (pin "2") (pinfunction "2_2") (pintype "passive"))
      (node (ref "IC2") (pin "6") (pinfunction "C1-_6") (pintype "bidirectional"))
    )
    (net (code "24") (name "Net-(IC3-Y)") (class "Default")
      (node (ref "IC3") (pin "4") (pinfunction "Y_4") (pintype "bidirectional"))
      (node (ref "R8") (pin "1") (pinfunction "1_1") (pintype "passive"))
    )
    (net (code "25") (name "Net-(IC4A-X0)") (class "Default")
      (node (ref "IC4") (pin "13") (pinfunction "X0_13") (pintype "bidirectional"))
      (node (ref "Y1") (pin "1") (pinfunction "1_1") (pintype "bidirectional"))
    )
    (net (code "26") (name "Net-(IC4A-X1)") (class "Default")
      (node (ref "IC4") (pin "14") (pinfunction "X1_14") (pintype "bidirectional"))
      (node (ref "Y2") (pin "1") (pinfunction "1_1") (pintype "bidirectional"))
    )
    (net (code "27") (name "Net-(IC4A-X2)") (class "Default")
      (node (ref "IC4") (pin "15") (pinfunction "X2_15") (pintype "bidirectional"))
      (node (ref "Y3") (pin "1") (pinfunction "1_1") (pintype "bidirectional"))
    )
    (net (code "28") (name "Net-(IC4A-X3)") (class "Default")
      (node (ref "IC4") (pin "12") (pinfunction "X3_12") (pintype "bidirectional"))
      (node (ref "Y0") (pin "1") (pinfunction "1_1") (pintype "bidirectional"))
    )
    (net (code "29") (name "Net-(IC4A-X4)") (class "Default")
      (node (ref "IC4") (pin "1") (pinfunction "X4_1") (pintype "bidirectional"))
      (node (ref "Y7") (pin "1") (pinfunction "1_1") (pintype "bidirectional"))
    )
    (net (code "30") (name "Net-(IC4A-X5)") (class "Default")
      (node (ref "IC4") (pin "5") (pinfunction "X5_5") (pintype "bidirectional"))
      (node (ref "Y4") (pin "1") (pinfunction "1_1") (pintype "bidirectional"))
    )
    (net (code "31") (name "Net-(IC4A-X6)") (class "Default")
      (node (ref "IC4") (pin "2") (pinfunction "X6_2") (pintype "bidirectional"))
      (node (ref "Y6") (pin "1") (pinfunction "1_1") (pintype "bidirectional"))
    )
    (net (code "32") (name "Net-(IC4A-X7)") (class "Default")
      (node (ref "IC4") (pin "4") (pinfunction "X7_4") (pintype "bidirectional"))
      (node (ref "Y5") (pin "1") (pinfunction "1_1") (pintype "bidirectional"))
    )
    (net (code "33") (name "Net-(IC5A-X0)") (class "Default")
      (node (ref "IC5") (pin "13") (pinfunction "X0_13") (pintype "bidirectional"))
      (node (ref "Y9") (pin "1") (pinfunction "1_1") (pintype "bidirectional"))
    )
    (net (code "34") (name "Net-(IC5A-X1)") (class "Default")
      (node (ref "IC5") (pin "14") (pinfunction "X1_14") (pintype "bidirectional"))
      (node (ref "X13") (pin "1") (pinfunction "1_1") (pintype "bidirectional"))
    )
    (net (code "35") (name "Net-(IC5A-X2)") (class "Default")
      (node (ref "IC5") (pin "15") (pinfunction "X2_15") (pintype "bidirectional"))
      (node (ref "X12") (pin "1") (pinfunction "1_1") (pintype "bidirectional"))
    )
    (net (code "36") (name "Net-(IC5A-X3)") (class "Default")
      (node (ref "IC5") (pin "12") (pinfunction "X3_12") (pintype "bidirectional"))
      (node (ref "Y8") (pin "1") (pinfunction "1_1") (pintype "bidirectional"))
    )
    (net (code "37") (name "Net-(IC5A-X4)") (class "Default")
      (node (ref "IC5") (pin "1") (pinfunction "X4_1") (pintype "bidirectional"))
      (node (ref "X11") (pin "1") (pinfunction "1_1") (pintype "bidirectional"))
    )
    (net (code "38") (name "Net-(IC5A-X5)") (class "Default")
      (node (ref "IC5") (pin "5") (pinfunction "X5_5") (pintype "bidirectional"))
      (node (ref "X8") (pin "1") (pinfunction "1_1") (pintype "bidirectional"))
    )
    (net (code "39") (name "Net-(IC5A-X6)") (class "Default")
      (node (ref "IC5") (pin "2") (pinfunction "X6_2") (pintype "bidirectional"))
      (node (ref "X10") (pin "1") (pinfunction "1_1") (pintype "bidirectional"))
    )
    (net (code "40") (name "Net-(IC5A-X7)") (class "Default")
      (node (ref "IC5") (pin "4") (pinfunction "X7_4") (pintype "bidirectional"))
      (node (ref "X9") (pin "1") (pinfunction "1_1") (pintype "bidirectional"))
    )
    (net (code "41") (name "Net-(IC6A-X0)") (class "Default")
      (node (ref "IC6") (pin "13") (pinfunction "X0_13") (pintype "bidirectional"))
      (node (ref "X5") (pin "1") (pinfunction "1_1") (pintype "bidirectional"))
    )
    (net (code "42") (name "Net-(IC6A-X1)") (class "Default")
      (node (ref "IC6") (pin "14") (pinfunction "X1_14") (pintype "bidirectional"))
      (node (ref "X6") (pin "1") (pinfunction "1_1") (pintype "bidirectional"))
    )
    (net (code "43") (name "Net-(IC6A-X2)") (class "Default")
      (node (ref "IC6") (pin "15") (pinfunction "X2_15") (pintype "bidirectional"))
      (node (ref "X7") (pin "1") (pinfunction "1_1") (pintype "bidirectional"))
    )
    (net (code "44") (name "Net-(IC6A-X3)") (class "Default")
      (node (ref "IC6") (pin "12") (pinfunction "X3_12") (pintype "bidirectional"))
      (node (ref "X4") (pin "1") (pinfunction "1_1") (pintype "bidirectional"))
    )
    (net (code "45") (name "Net-(IC6A-X4)") (class "Default")
      (node (ref "IC6") (pin "1") (pinfunction "X4_1") (pintype "bidirectional"))
      (node (ref "X3") (pin "1") (pinfunction "1_1") (pintype "bidirectional"))
    )
    (net (code "46") (name "Net-(IC6A-X5)") (class "Default")
      (node (ref "IC6") (pin "5") (pinfunction "X5_5") (pintype "bidirectional"))
      (node (ref "X0") (pin "1") (pinfunction "1_1") (pintype "bidirectional"))
    )
    (net (code "47") (name "Net-(IC6A-X6)") (class "Default")
      (node (ref "IC6") (pin "2") (pinfunction "X6_2") (pintype "bidirectional"))
      (node (ref "X2") (pin "1") (pinfunction "1_1") (pintype "bidirectional"))
    )
    (net (code "48") (name "Net-(IC6A-X7)") (class "Default")
      (node (ref "IC6") (pin "4") (pinfunction "X7_4") (pintype "bidirectional"))
      (node (ref "X1") (pin "1") (pinfunction "1_1") (pintype "bidirectional"))
    )
    (net (code "49") (name "Net-(IC7-COM)") (class "Default")
      (node (ref "IC7") (pin "1") (pinfunction "COM_1") (pintype "bidirectional"))
      (node (ref "IC8") (pin "3") (pinfunction "+IN_3") (pintype "input"))
      (node (ref "R10") (pin "2") (pinfunction "2_2") (pintype "passive"))
    )
    (net (code "50") (name "Net-(IC8A--IN)") (class "Default")
      (node (ref "IC8") (pin "2") (pinfunction "-IN_2") (pintype "input"))
      (node (ref "R11") (pin "2") (pinfunction "2_2") (pintype "passive"))
      (node (ref "R12") (pin "1") (pinfunction "1_1") (pintype "passive"))
    )
    (net (code "51") (name "Net-(IC8A-OUT)") (class "Default")
      (node (ref "IC8") (pin "1") (pinfunction "OUT_1") (pintype "output"))
      (node (ref "IC8") (pin "5") (pinfunction "+IN_5") (pintype "input"))
      (node (ref "R12") (pin "2") (pinfunction "2_2") (pintype "passive"))
    )
    (net (code "52") (name "Net-(IC8B--IN)") (class "Default")
      (node (ref "IC8") (pin "6") (pinfunction "-IN_6") (pintype "input"))
      (node (ref "R13") (pin "2") (pinfunction "2_2") (pintype "passive"))
      (node (ref "R14") (pin "1") (pinfunction "1_1") (pintype "passive"))
    )
    (net (code "53") (name "Net-(IC8B-OUT)") (class "Default")
      (node (ref "IC8") (pin "7") (pinfunction "OUT_7") (pintype "output"))
      (node (ref "R14") (pin "2") (pinfunction "2_2") (pintype "passive"))
      (node (ref "R15") (pin "1") (pinfunction "1_1") (pintype "passive"))
      (node (ref "R17") (pin "1") (pinfunction "1_1") (pintype "passive"))
    )
    (net (code "54") (name "Net-(IC9A--IN)") (class "Default")
      (node (ref "D3") (pin "2") (pinfunction "2_2") (pintype "passive"))
      (node (ref "IC9") (pin "2") (pinfunction "-IN_2") (pintype "input"))
      (node (ref "R15") (pin "2") (pinfunction "2_2") (pintype "passive"))
      (node (ref "R16") (pin "1") (pinfunction "1_1") (pintype "passive"))
    )
    (net (code "55") (name "Net-(IC9A-OUT)") (class "Default")
      (node (ref "D3") (pin "1") (pinfunction "1_1") (pintype "passive"))
      (node (ref "D4") (pin "2") (pinfunction "2_2") (pintype "passive"))
      (node (ref "IC9") (pin "1") (pinfunction "OUT_1") (pintype "output"))
    )
    (net (code "56") (name "Net-(IC9B--IN)") (class "Default")
      (node (ref "IC9") (pin "6") (pinfunction "-IN_6") (pintype "input"))
      (node (ref "R17") (pin "2") (pinfunction "2_2") (pintype "passive"))
      (node (ref "R18") (pin "1") (pinfunction "1_1") (pintype "passive"))
      (node (ref "R19") (pin "1") (pinfunction "1_1") (pintype "passive"))
    )
    (net (code "57") (name "Net-(IC10-OUT)") (class "Default")
      (node (ref "IC10") (pin "5") (pinfunction "OUT_5") (pintype "output"))
      (node (ref "R21") (pin "1") (pinfunction "1_1") (pintype "passive"))
    )
    (net (code "58") (name "Net-(IC11A-+IN)") (class "Default")
      (node (ref "IC11") (pin "3") (pinfunction "+IN_3") (pintype "input"))
      (node (ref "IC9") (pin "7") (pinfunction "OUT_7") (pintype "output"))
      (node (ref "R19") (pin "2") (pinfunction "2_2") (pintype "passive"))
    )
    (net (code "59") (name "Net-(IC11A--IN)") (class "Default")
      (node (ref "D5") (pin "2") (pinfunction "2_2") (pintype "passive"))
      (node (ref "IC11") (pin "2") (pinfunction "-IN_2") (pintype "input"))
      (node (ref "R22") (pin "1") (pinfunction "1_1") (pintype "passive"))
    )
    (net (code "60") (name "Net-(IC11A-OUT)") (class "Default")
      (node (ref "D5") (pin "1") (pinfunction "1_1") (pintype "passive"))
      (node (ref "IC11") (pin "1") (pinfunction "OUT_1") (pintype "output"))
    )
    (net (code "61") (name "Net-(IC11B-+IN)") (class "Default")
      (node (ref "C25") (pin "1") (pinfunction "1_1") (pintype "passive"))
      (node (ref "IC11") (pin "5") (pinfunction "+IN_5") (pintype "input"))
      (node (ref "R22") (pin "2") (pinfunction "2_2") (pintype "passive"))
      (node (ref "R24") (pin "2") (pinfunction "2_2") (pintype "passive"))
    )
    (net (code "62") (name "Net-(IC11B--IN)") (class "Default")
      (node (ref "IC11") (pin "6") (pinfunction "-IN_6") (pintype "input"))
      (node (ref "IC11") (pin "7") (pinfunction "OUT_7") (pintype "output"))
      (node (ref "IC12") (pin "2") (pinfunction "IN+_2") (pintype "input"))
    )
    (net (code "63") (name "Net-(J1-CC1)") (class "Default")
      (node (ref "J1") (pin "A5") (pinfunction "CC1_A5") (pintype "bidirectional"))
      (node (ref "R1") (pin "1") (pinfunction "1_1") (pintype "passive"))
    )
    (net (code "64") (name "Net-(J1-CC2)") (class "Default")
      (node (ref "J1") (pin "B5") (pinfunction "CC2_B5") (pintype "bidirectional"))
      (node (ref "R2") (pin "1") (pinfunction "1_1") (pintype "passive"))
    )
    (net (code "65") (name "Net-(J1-DN-PadA7)") (class "Default")
      (node (ref "J1") (pin "A7") (pinfunction "DN_A7") (pintype "bidirectional"))
      (node (ref "J1") (pin "B7") (pinfunction "DN_B7") (pintype "bidirectional"))
      (node (ref "R3") (pin "1") (pinfunction "1_1") (pintype "passive"))
    )
    (net (code "66") (name "Net-(J1-DP-PadA6)") (class "Default")
      (node (ref "J1") (pin "A6") (pinfunction "DP_A6") (pintype "bidirectional"))
      (node (ref "J1") (pin "B6") (pinfunction "DP_B6") (pintype "bidirectional"))
      (node (ref "R4") (pin "1") (pinfunction "1_1") (pintype "passive"))
    )
    (net (code "67") (name "Net-(Q1-D)") (class "Default")
      (node (ref "Q1") (pin "P$3") (pinfunction "D_P$3") (pintype "passive"))
      (node (ref "R24") (pin "1") (pinfunction "1_1") (pintype "passive"))
    )
    (net (code "68") (name "Net-(Q1-G)") (class "Default")
      (node (ref "Q1") (pin "P$1") (pinfunction "G_P$1") (pintype "passive"))
      (node (ref "R21") (pin "2") (pinfunction "2_2") (pintype "passive"))
      (node (ref "R23") (pin "1") (pinfunction "1_1") (pintype "passive"))
    )
    (net (code "69") (name "OUT") (class "Default")
      (node (ref "IC1") (pin "13") (pinfunction "PD7_(~{HWB})_13") (pintype "bidirectional"))
      (node (ref "IC3") (pin "2") (pinfunction "A_2") (pintype "bidirectional"))
      (node (ref "R5") (pin "2") (pinfunction "2_2") (pintype "passive"))
    )
    (net (code "70") (name "OUT_OE") (class "Default")
      (node (ref "IC1") (pin "12") (pinfunction "PD6_12") (pintype "bidirectional"))
      (node (ref "IC3") (pin "1") (pinfunction "~{OE}_1") (pintype "bidirectional"))
      (node (ref "IC7") (pin "6") (pinfunction "IN_6") (pintype "bidirectional"))
      (node (ref "R9") (pin "2") (pinfunction "2_2") (pintype "passive"))
    )
    (net (code "71") (name "PEAK_DRAIN") (class "Default")
      (node (ref "IC1") (pin "5") (pinfunction "PC2_5") (pintype "bidirectional"))
      (node (ref "IC10") (pin "3") (pinfunction "IN_3") (pintype "input"))
      (node (ref "R20") (pin "2") (pinfunction "2_2") (pintype "passive"))
    )
    (net (code "72") (name "S0") (class "Default")
      (node (ref "IC1") (pin "6") (pinfunction "PD0_6") (pintype "bidirectional"))
      (node (ref "IC4") (pin "11") (pinfunction "A_11") (pintype "input"))
      (node (ref "IC5") (pin "11") (pinfunction "A_11") (pintype "input"))
      (node (ref "IC6") (pin "11") (pinfunction "A_11") (pintype "input"))
    )
    (net (code "73") (name "S1") (class "Default")
      (node (ref "IC1") (pin "7") (pinfunction "PD1_7") (pintype "bidirectional"))
      (node (ref "IC4") (pin "10") (pinfunction "B_10") (pintype "input"))
      (node (ref "IC5") (pin "10") (pinfunction "B_10") (pintype "input"))
      (node (ref "IC6") (pin "10") (pinfunction "B_10") (pintype "input"))
    )
    (net (code "74") (name "S2") (class "Default")
      (node (ref "IC1") (pin "8") (pinfunction "PD2_8") (pintype "bidirectional"))
      (node (ref "IC4") (pin "9") (pinfunction "C_9") (pintype "input"))
      (node (ref "IC5") (pin "9") (pinfunction "C_9") (pintype "input"))
      (node (ref "IC6") (pin "9") (pinfunction "C_9") (pintype "input"))
    )
    (net (code "75") (name "SCLK") (class "Default")
      (node (ref "IC1") (pin "15") (pinfunction "(SCLK)_PB1_15") (pintype "bidirectional"))
      (node (ref "IC12") (pin "7") (pinfunction "CLK_7") (pintype "input"))
    )
    (net (code "76") (name "SIGNAL") (class "Default")
      (node (ref "D1") (pin "2") (pinfunction "2_2") (pintype "passive"))
      (node (ref "FB2") (pin "1") (pinfunction "1_1") (pintype "passive"))
      (node (ref "IC4") (pin "3") (pinfunction "X_3") (pintype "bidirectional"))
      (node (ref "IC5") (pin "3") (pinfunction "X_3") (pintype "bidirectional"))
      (node (ref "IC6") (pin "3") (pinfunction "X_3") (pintype "bidirectional"))
      (node (ref "IC7") (pin "8") (pinfunction "NO_8") (pintype "bidirectional"))
    )
    (net (code "77") (name "unconnected-(IC1-(MOSI)_PB2-Pad16)") (class "Default")
      (node (ref "IC1") (pin "16") (pinfunction "(MOSI)_PB2_16") (pintype "bidirectional"))
    )
    (net (code "78") (name "unconnected-(IC1-PB5-Pad19)") (class "Default")
      (node (ref "IC1") (pin "19") (pinfunction "PB5_19") (pintype "bidirectional"))
    )
    (net (code "79") (name "unconnected-(IC1-PB6-Pad20)") (class "Default")
      (node (ref "IC1") (pin "20") (pinfunction "PB6_20") (pintype "bidirectional"))
    )
    (net (code "80") (name "unconnected-(IC1-PB7-Pad21)") (class "Default")
      (node (ref "IC1") (pin "21") (pinfunction "PB7_21") (pintype "bidirectional"))
    )
    (net (code "81") (name "unconnected-(IC1-PC4-Pad26)") (class "Default")
      (node (ref "IC1") (pin "26") (pinfunction "PC4_26") (pintype "bidirectional"))
    )
    (net (code "82") (name "unconnected-(IC1-PC5-Pad25)") (class "Default")
      (node (ref "IC1") (pin "25") (pinfunction "PC5_25") (pintype "bidirectional"))
    )
    (net (code "83") (name "unconnected-(IC1-PC6-Pad23)") (class "Default")
      (node (ref "IC1") (pin "23") (pinfunction "PC6_23") (pintype "bidirectional"))
    )
    (net (code "84") (name "unconnected-(IC1-PC7-Pad22)") (class "Default")
      (node (ref "IC1") (pin "22") (pinfunction "PC7_22") (pintype "bidirectional"))
    )
    (net (code "85") (name "unconnected-(J1-SBU1-PadA8)") (class "Default")
      (node (ref "J1") (pin "A8") (pinfunction "SBU1_A8") (pintype "bidirectional"))
    )
    (net (code "86") (name "unconnected-(J1-SBU2-PadB8)") (class "Default")
      (node (ref "J1") (pin "B8") (pinfunction "SBU2_B8") (pintype "bidirectional"))
    )
  )
)
